# sun_bear.net
KiCad netlist of a schematic drawn in EAGLE
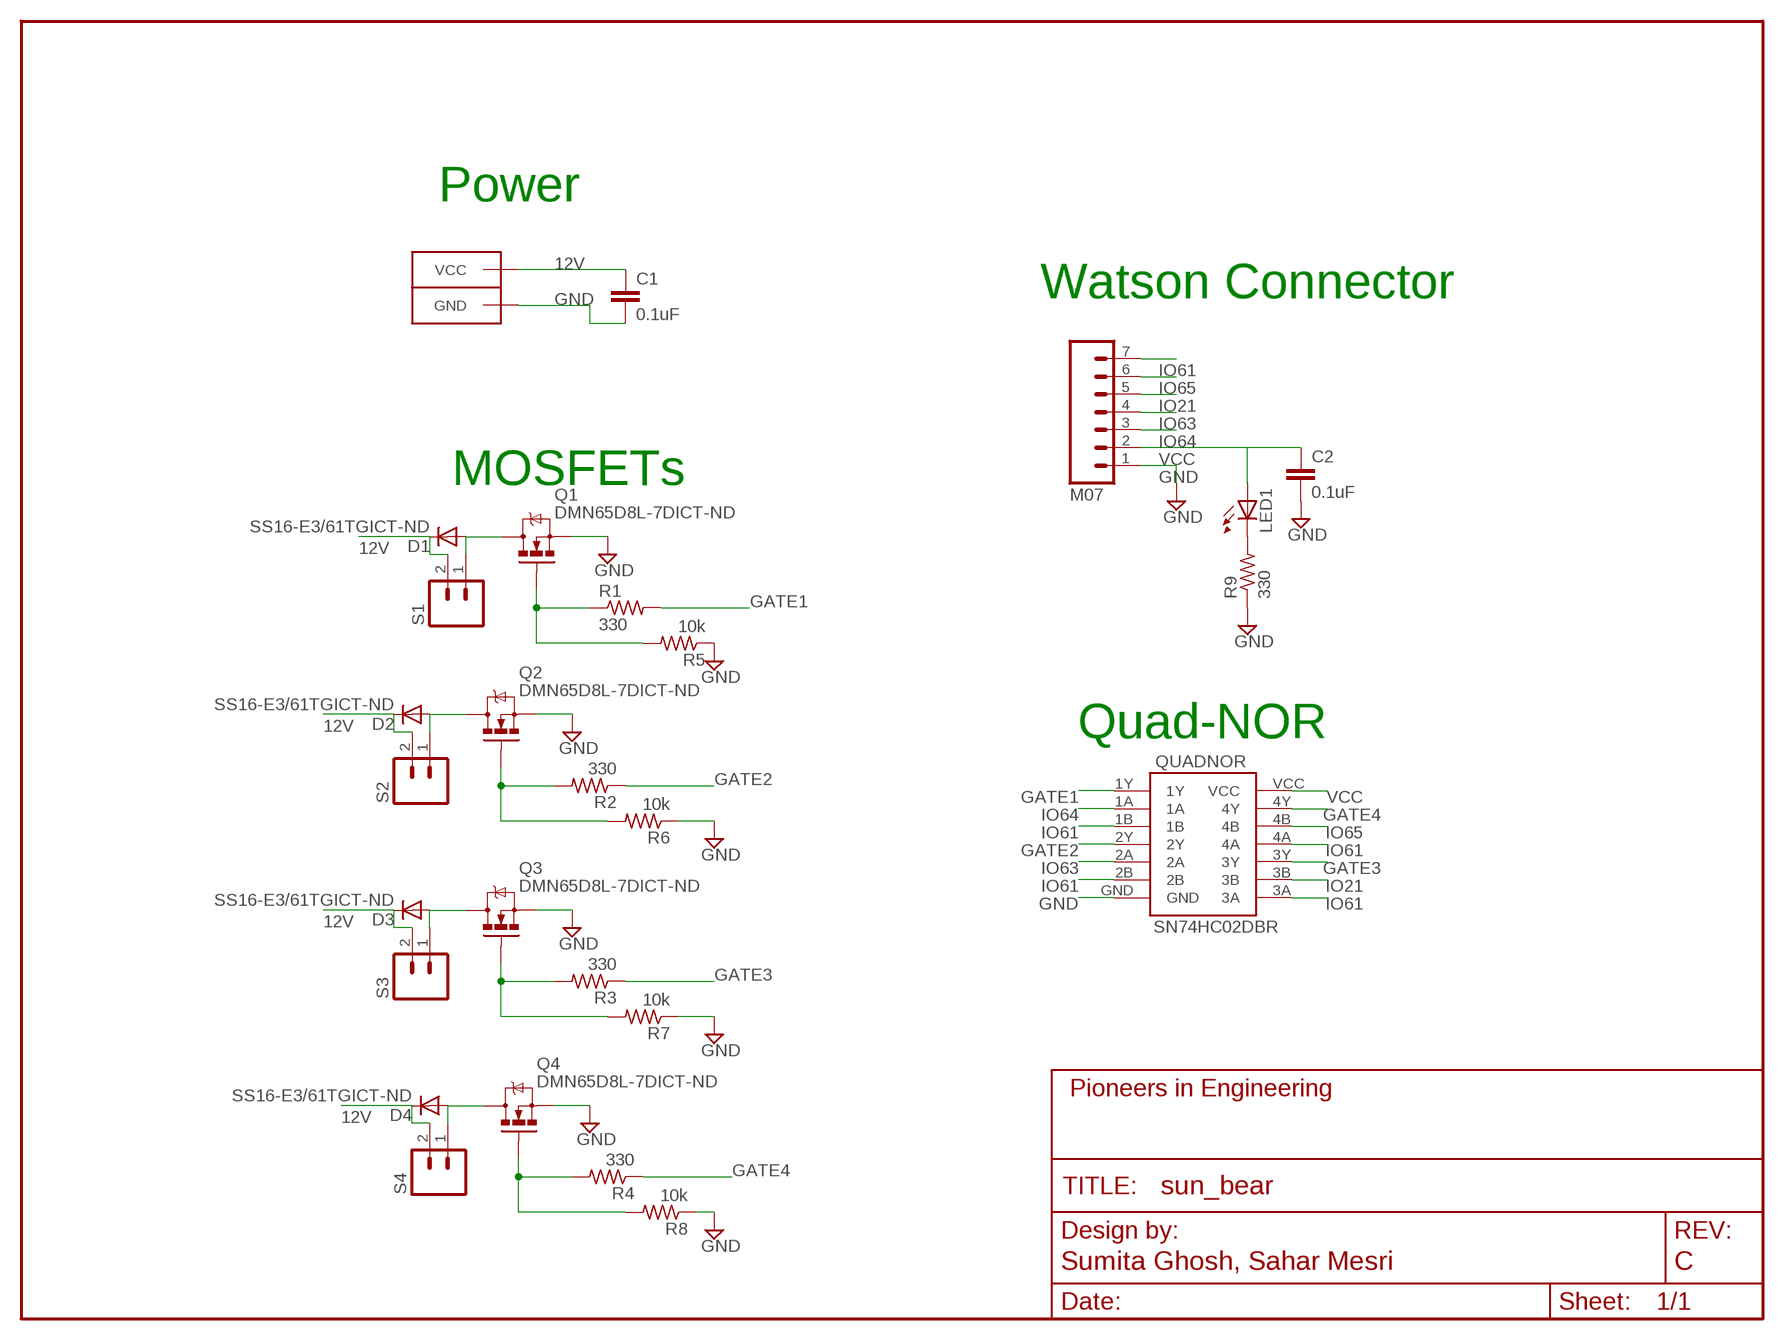
[diagram p0: schematic, sheet 1]

(export (version "E")
  (design (tool "Eeschema 10.0.6"))
  (components
    (comp (ref "C1")
      (value "0.1uF")
      (footprint "eagle-import:0603-CAP")
      (libsource (lib "eagle-import") (part "CAP0603-CAP"))
    )
    (comp (ref "C2")
      (value "0.1uF")
      (footprint "eagle-import:0603-CAP")
      (libsource (lib "eagle-import") (part "CAP0603-CAP"))
    )
    (comp (ref "D1")
      (value "SS16-E3/61TGICT-ND")
      (footprint "eagle-import:SMA-DIODE_ALT")
      (libsource (lib "eagle-import") (part "DIODESMA-ALT"))
    )
    (comp (ref "D2")
      (value "SS16-E3/61TGICT-ND")
      (footprint "eagle-import:SMA-DIODE_ALT")
      (libsource (lib "eagle-import") (part "DIODESMA-ALT"))
    )
    (comp (ref "D3")
      (value "SS16-E3/61TGICT-ND")
      (footprint "eagle-import:SMA-DIODE_ALT")
      (libsource (lib "eagle-import") (part "DIODESMA-ALT"))
    )
    (comp (ref "D4")
      (value "SS16-E3/61TGICT-ND")
      (footprint "eagle-import:SMA-DIODE_ALT")
      (libsource (lib "eagle-import") (part "DIODESMA-ALT"))
    )
    (comp (ref "LED1")
      (value "LED0805")
      (footprint "eagle-import:LED-0805")
      (libsource (lib "eagle-import") (part "LED0805"))
    )
    (comp (ref "POWER")
      (value "ANDERSONVERTICAL")
      (footprint "eagle-import:ANDERSON_VERTICAL")
      (fields (field (name "PARTNUMBER") "1377G3"))
      (libsource (lib "eagle-import") (part "ANDERSONVERTICAL"))
    )
    (comp (ref "Q1")
      (value "DMN65D8L-7DICT-ND")
      (footprint "eagle-import:SOT23-3")
      (libsource (lib "eagle-import") (part "MOSFET-NCHANNELSMD"))
    )
    (comp (ref "Q2")
      (value "DMN65D8L-7DICT-ND")
      (footprint "eagle-import:SOT23-3")
      (libsource (lib "eagle-import") (part "MOSFET-NCHANNELSMD"))
    )
    (comp (ref "Q3")
      (value "DMN65D8L-7DICT-ND")
      (footprint "eagle-import:SOT23-3")
      (libsource (lib "eagle-import") (part "MOSFET-NCHANNELSMD"))
    )
    (comp (ref "Q4")
      (value "DMN65D8L-7DICT-ND")
      (footprint "eagle-import:SOT23-3")
      (libsource (lib "eagle-import") (part "MOSFET-NCHANNELSMD"))
    )
    (comp (ref "QUADNOR")
      (value "SN74HC02DBR")
      (footprint "eagle-import:QUADNOR")
      (fields (field (name "PARTNUMBER") "296-8204-1-ND"))
      (libsource (lib "eagle-import") (part "SN74HC02DBR"))
    )
    (comp (ref "R1")
      (value "330")
      (footprint "eagle-import:R0603")
      (libsource (lib "eagle-import") (part "R-US_R0603"))
    )
    (comp (ref "R2")
      (value "330")
      (footprint "eagle-import:R0603")
      (libsource (lib "eagle-import") (part "R-US_R0603"))
    )
    (comp (ref "R3")
      (value "330")
      (footprint "eagle-import:R0603")
      (libsource (lib "eagle-import") (part "R-US_R0603"))
    )
    (comp (ref "R4")
      (value "330")
      (footprint "eagle-import:R0603")
      (libsource (lib "eagle-import") (part "R-US_R0603"))
    )
    (comp (ref "R5")
      (value "10k")
      (footprint "eagle-import:R0603")
      (libsource (lib "eagle-import") (part "R-US_R0603"))
    )
    (comp (ref "R6")
      (value "10k")
      (footprint "eagle-import:R0603")
      (libsource (lib "eagle-import") (part "R-US_R0603"))
    )
    (comp (ref "R7")
      (value "10k")
      (footprint "eagle-import:R0603")
      (libsource (lib "eagle-import") (part "R-US_R0603"))
    )
    (comp (ref "R8")
      (value "10k")
      (footprint "eagle-import:R0603")
      (libsource (lib "eagle-import") (part "R-US_R0603"))
    )
    (comp (ref "R9")
      (value "330")
      (footprint "eagle-import:R0603")
      (libsource (lib "eagle-import") (part "R-US_R0603"))
    )
    (comp (ref "S1")
      (value "M021X02-MTA")
      (footprint "eagle-import:1X02-MTA")
      (fields (field (name "PARTNUMBER") "A1921-ND"))
      (libsource (lib "eagle-import") (part "M021X02-MTA"))
    )
    (comp (ref "S2")
      (value "M021X02-MTA")
      (footprint "eagle-import:1X02-MTA")
      (fields (field (name "PARTNUMBER") "A1921-ND"))
      (libsource (lib "eagle-import") (part "M021X02-MTA"))
    )
    (comp (ref "S3")
      (value "M021X02-MTA")
      (footprint "eagle-import:1X02-MTA")
      (fields (field (name "PARTNUMBER") "A1921-ND"))
      (libsource (lib "eagle-import") (part "M021X02-MTA"))
    )
    (comp (ref "S4")
      (value "M021X02-MTA")
      (footprint "eagle-import:1X02-MTA")
      (fields (field (name "PARTNUMBER") "A1921-ND"))
      (libsource (lib "eagle-import") (part "M021X02-MTA"))
    )
    (comp (ref "WATSON")
      (value "M07")
      (footprint "eagle-import:1X07-MTA")
      (fields (field (name "PARTNUMBER") "A19472-ND"))
      (libsource (lib "eagle-import") (part "M07"))
    )
  )
  (nets
    (net (code "1") (name "/12V") (class "Default")
      (node (ref "C1") (pin "1") (pinfunction "1_1") (pintype "passive"))
      (node (ref "D1") (pin "C") (pinfunction "C_C") (pintype "passive"))
      (node (ref "D2") (pin "C") (pinfunction "C_C") (pintype "passive"))
      (node (ref "D3") (pin "C") (pinfunction "C_C") (pintype "passive"))
      (node (ref "D4") (pin "C") (pinfunction "C_C") (pintype "passive"))
      (node (ref "POWER") (pin "PIN2") (pinfunction "VCC_PIN2") (pintype "bidirectional"))
      (node (ref "S1") (pin "2") (pinfunction "2_2") (pintype "passive"))
      (node (ref "S2") (pin "2") (pinfunction "2_2") (pintype "passive"))
      (node (ref "S3") (pin "2") (pinfunction "2_2") (pintype "passive"))
      (node (ref "S4") (pin "2") (pinfunction "2_2") (pintype "passive"))
    )
    (net (code "2") (name "/GATE1") (class "Default")
      (node (ref "QUADNOR") (pin "1Y") (pinfunction "1Y_1Y") (pintype "bidirectional"))
      (node (ref "R1") (pin "2") (pinfunction "2_2") (pintype "passive"))
    )
    (net (code "3") (name "/GATE2") (class "Default")
      (node (ref "QUADNOR") (pin "2Y") (pinfunction "2Y_2Y") (pintype "bidirectional"))
      (node (ref "R2") (pin "1") (pinfunction "1_1") (pintype "passive"))
    )
    (net (code "4") (name "/GATE3") (class "Default")
      (node (ref "QUADNOR") (pin "3Y") (pinfunction "3Y_3Y") (pintype "bidirectional"))
      (node (ref "R3") (pin "1") (pinfunction "1_1") (pintype "passive"))
    )
    (net (code "5") (name "/GATE4") (class "Default")
      (node (ref "QUADNOR") (pin "4Y") (pinfunction "4Y_4Y") (pintype "bidirectional"))
      (node (ref "R4") (pin "1") (pinfunction "1_1") (pintype "passive"))
    )
    (net (code "6") (name "/IO21") (class "Default")
      (node (ref "QUADNOR") (pin "3B") (pinfunction "3B_3B") (pintype "bidirectional"))
      (node (ref "WATSON") (pin "5") (pinfunction "5_5") (pintype "passive"))
    )
    (net (code "7") (name "/IO61") (class "Default")
      (node (ref "QUADNOR") (pin "1B") (pinfunction "1B_1B") (pintype "bidirectional"))
      (node (ref "QUADNOR") (pin "2B") (pinfunction "2B_2B") (pintype "bidirectional"))
      (node (ref "QUADNOR") (pin "3A") (pinfunction "3A_3A") (pintype "bidirectional"))
      (node (ref "QUADNOR") (pin "4A") (pinfunction "4A_4A") (pintype "bidirectional"))
      (node (ref "WATSON") (pin "7") (pinfunction "7_7") (pintype "passive"))
    )
    (net (code "8") (name "/IO63") (class "Default")
      (node (ref "QUADNOR") (pin "2A") (pinfunction "2A_2A") (pintype "bidirectional"))
      (node (ref "WATSON") (pin "4") (pinfunction "4_4") (pintype "passive"))
    )
    (net (code "9") (name "/IO64") (class "Default")
      (node (ref "QUADNOR") (pin "1A") (pinfunction "1A_1A") (pintype "bidirectional"))
      (node (ref "WATSON") (pin "3") (pinfunction "3_3") (pintype "passive"))
    )
    (net (code "10") (name "/IO65") (class "Default")
      (node (ref "QUADNOR") (pin "4B") (pinfunction "4B_4B") (pintype "bidirectional"))
      (node (ref "WATSON") (pin "6") (pinfunction "6_6") (pintype "passive"))
    )
    (net (code "11") (name "/VCC") (class "Default")
      (node (ref "C2") (pin "1") (pinfunction "1_1") (pintype "passive"))
      (node (ref "LED1") (pin "A") (pinfunction "A_A") (pintype "passive"))
      (node (ref "QUADNOR") (pin "VCC") (pinfunction "VCC_VCC") (pintype "bidirectional"))
      (node (ref "WATSON") (pin "2") (pinfunction "2_2") (pintype "passive"))
    )
    (net (code "12") (name "GND") (class "Default")
      (node (ref "C1") (pin "2") (pinfunction "2_2") (pintype "passive"))
      (node (ref "C2") (pin "2") (pinfunction "2_2") (pintype "passive"))
      (node (ref "POWER") (pin "PIN1") (pinfunction "GND_PIN1") (pintype "bidirectional"))
      (node (ref "Q1") (pin "2") (pinfunction "S_2") (pintype "passive"))
      (node (ref "Q2") (pin "2") (pinfunction "S_2") (pintype "passive"))
      (node (ref "Q3") (pin "2") (pinfunction "S_2") (pintype "passive"))
      (node (ref "Q4") (pin "2") (pinfunction "S_2") (pintype "passive"))
      (node (ref "QUADNOR") (pin "GND") (pinfunction "GND_GND") (pintype "bidirectional"))
      (node (ref "R5") (pin "1") (pinfunction "1_1") (pintype "passive"))
      (node (ref "R6") (pin "1") (pinfunction "1_1") (pintype "passive"))
      (node (ref "R7") (pin "1") (pinfunction "1_1") (pintype "passive"))
      (node (ref "R8") (pin "1") (pinfunction "1_1") (pintype "passive"))
      (node (ref "R9") (pin "1") (pinfunction "1_1") (pintype "passive"))
      (node (ref "WATSON") (pin "1") (pinfunction "1_1") (pintype "passive"))
    )
    (net (code "13") (name "Net-(LED1-PadC)") (class "Default")
      (node (ref "LED1") (pin "C") (pinfunction "C_C") (pintype "passive"))
      (node (ref "R9") (pin "2") (pinfunction "2_2") (pintype "passive"))
    )
    (net (code "14") (name "Net-(Q1-D)") (class "Default")
      (node (ref "D1") (pin "A") (pinfunction "A_A") (pintype "passive"))
      (node (ref "Q1") (pin "3") (pinfunction "D_3") (pintype "passive"))
      (node (ref "S1") (pin "1") (pinfunction "1_1") (pintype "passive"))
    )
    (net (code "15") (name "Net-(Q1-G)") (class "Default")
      (node (ref "Q1") (pin "1") (pinfunction "G_1") (pintype "passive"))
      (node (ref "R1") (pin "1") (pinfunction "1_1") (pintype "passive"))
      (node (ref "R5") (pin "2") (pinfunction "2_2") (pintype "passive"))
    )
    (net (code "16") (name "Net-(Q2-D)") (class "Default")
      (node (ref "D2") (pin "A") (pinfunction "A_A") (pintype "passive"))
      (node (ref "Q2") (pin "3") (pinfunction "D_3") (pintype "passive"))
      (node (ref "S2") (pin "1") (pinfunction "1_1") (pintype "passive"))
    )
    (net (code "17") (name "Net-(Q2-G)") (class "Default")
      (node (ref "Q2") (pin "1") (pinfunction "G_1") (pintype "passive"))
      (node (ref "R2") (pin "2") (pinfunction "2_2") (pintype "passive"))
      (node (ref "R6") (pin "2") (pinfunction "2_2") (pintype "passive"))
    )
    (net (code "18") (name "Net-(Q3-D)") (class "Default")
      (node (ref "D3") (pin "A") (pinfunction "A_A") (pintype "passive"))
      (node (ref "Q3") (pin "3") (pinfunction "D_3") (pintype "passive"))
      (node (ref "S3") (pin "1") (pinfunction "1_1") (pintype "passive"))
    )
    (net (code "19") (name "Net-(Q3-G)") (class "Default")
      (node (ref "Q3") (pin "1") (pinfunction "G_1") (pintype "passive"))
      (node (ref "R3") (pin "2") (pinfunction "2_2") (pintype "passive"))
      (node (ref "R7") (pin "2") (pinfunction "2_2") (pintype "passive"))
    )
    (net (code "20") (name "Net-(Q4-D)") (class "Default")
      (node (ref "D4") (pin "A") (pinfunction "A_A") (pintype "passive"))
      (node (ref "Q4") (pin "3") (pinfunction "D_3") (pintype "passive"))
      (node (ref "S4") (pin "1") (pinfunction "1_1") (pintype "passive"))
    )
    (net (code "21") (name "Net-(Q4-G)") (class "Default")
      (node (ref "Q4") (pin "1") (pinfunction "G_1") (pintype "passive"))
      (node (ref "R4") (pin "2") (pinfunction "2_2") (pintype "passive"))
      (node (ref "R8") (pin "2") (pinfunction "2_2") (pintype "passive"))
    )
  )
)
